# CW308T_LPC55S69_Micro.net
KiCad netlist of a schematic drawn in Altium Designer
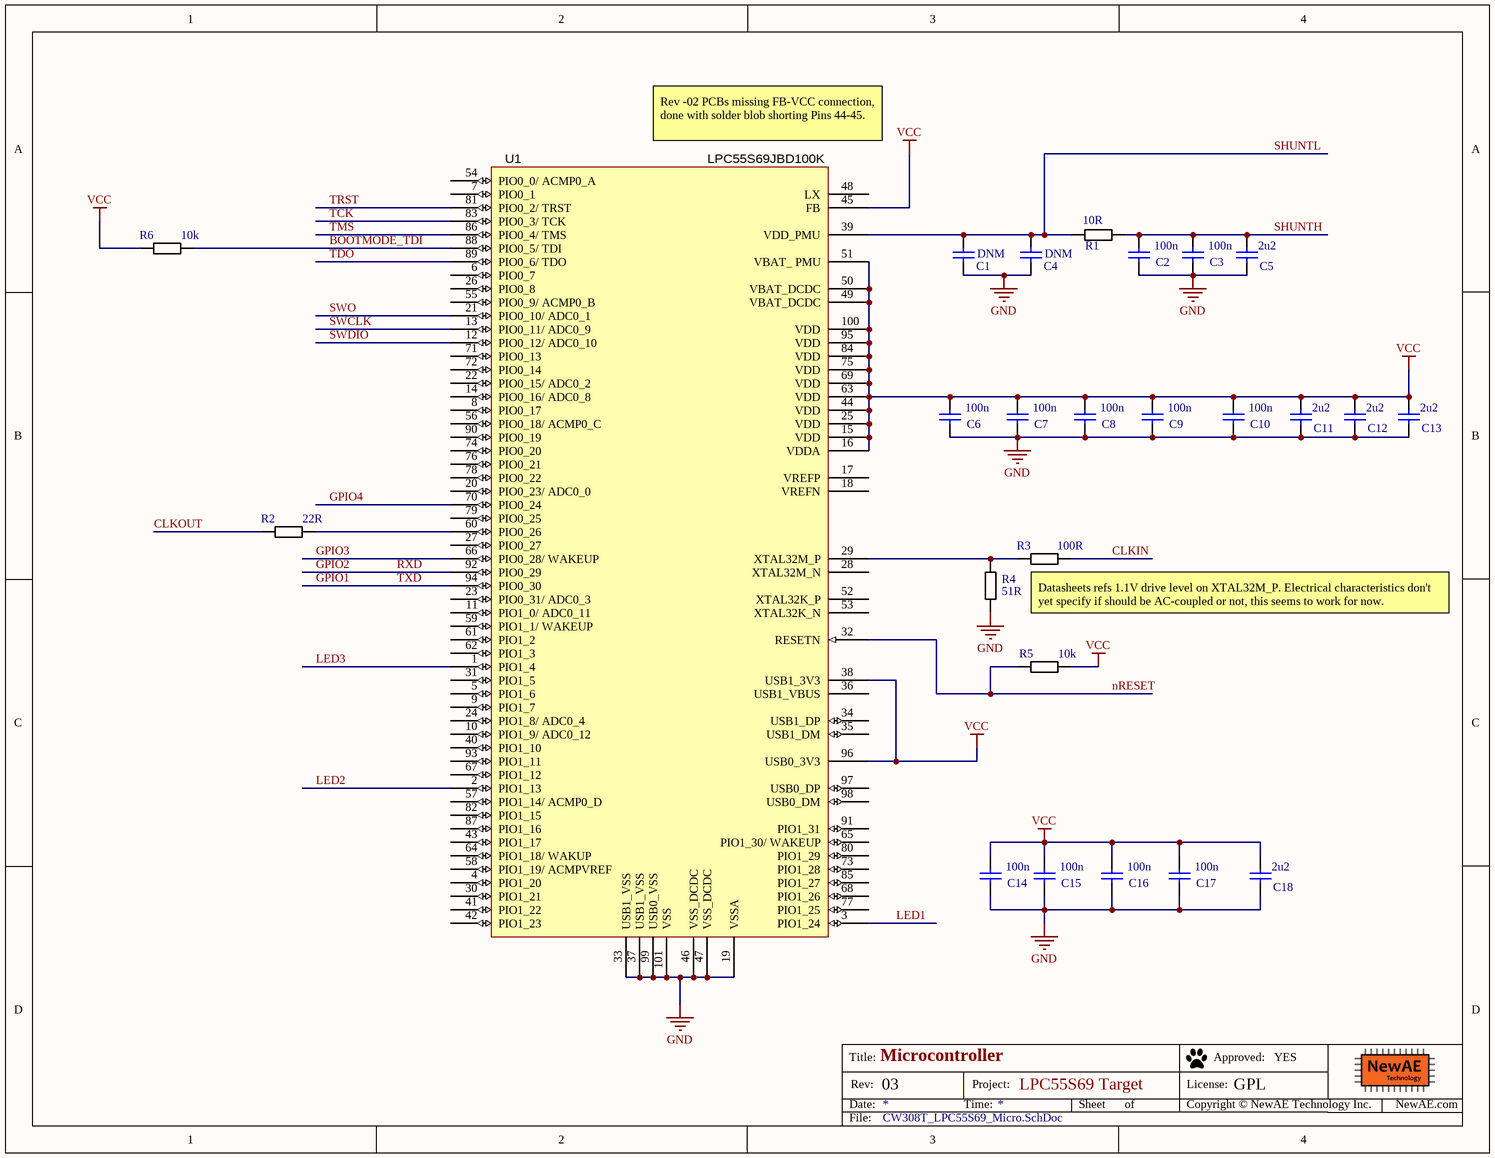
[diagram p0: CW308T_LPC55S69_Micro.SchDoc]

(export (version "E")
  (design (tool "Eeschema 10.0.6"))
  (components
    (comp (ref "C1")
      (value "DNM")
      (footprint "CAPC0603_M")
      (description "DNM, 0603")
      (fields (field (name "PART NUMBER") "CCHIP-DNM-0603"))
      (libsource (lib "NewAE_AltiumLib") (part "CAP"))
    )
    (comp (ref "C2")
      (value "100n")
      (footprint "CAPC0603_M")
      (description "100n, 0603")
      (fields (field (name "PART NUMBER") "CCHIP-100n-0603"))
      (libsource (lib "NewAE_AltiumLib") (part "CAP"))
    )
    (comp (ref "C3")
      (value "100n")
      (footprint "CAPC0603_M")
      (description "100n, 0603")
      (fields (field (name "PART NUMBER") "CCHIP-100n-0603"))
      (libsource (lib "NewAE_AltiumLib") (part "CAP"))
    )
    (comp (ref "C4")
      (value "DNM")
      (footprint "CAPC0603_M")
      (description "DNM, 0603")
      (fields (field (name "PART NUMBER") "CCHIP-DNM-0603"))
      (libsource (lib "NewAE_AltiumLib") (part "CAP"))
    )
    (comp (ref "C5")
      (value "2u2")
      (footprint "CAPC0603_M")
      (description "2u2, 0603")
      (fields (field (name "PART NUMBER") "CCHIP-2u2-0603"))
      (libsource (lib "NewAE_AltiumLib") (part "CAP"))
    )
    (comp (ref "C6")
      (value "100n")
      (footprint "CAPC0603_M")
      (description "100n, 0603")
      (fields (field (name "PART NUMBER") "CCHIP-100n-0603"))
      (libsource (lib "NewAE_AltiumLib") (part "CAP"))
    )
    (comp (ref "C7")
      (value "100n")
      (footprint "CAPC0603_M")
      (description "100n, 0603")
      (fields (field (name "PART NUMBER") "CCHIP-100n-0603"))
      (libsource (lib "NewAE_AltiumLib") (part "CAP"))
    )
    (comp (ref "C8")
      (value "100n")
      (footprint "CAPC0603_M")
      (description "100n, 0603")
      (fields (field (name "PART NUMBER") "CCHIP-100n-0603"))
      (libsource (lib "NewAE_AltiumLib") (part "CAP"))
    )
    (comp (ref "C9")
      (value "100n")
      (footprint "CAPC0603_M")
      (description "100n, 0603")
      (fields (field (name "PART NUMBER") "CCHIP-100n-0603"))
      (libsource (lib "NewAE_AltiumLib") (part "CAP"))
    )
    (comp (ref "C10")
      (value "100n")
      (footprint "CAPC0603_M")
      (description "100n, 0603")
      (fields (field (name "PART NUMBER") "CCHIP-100n-0603"))
      (libsource (lib "NewAE_AltiumLib") (part "CAP"))
    )
    (comp (ref "C11")
      (value "2u2")
      (footprint "CAPC0603_M")
      (description "2u2, 0603")
      (fields (field (name "PART NUMBER") "CCHIP-2u2-0603"))
      (libsource (lib "NewAE_AltiumLib") (part "CAP"))
    )
    (comp (ref "C12")
      (value "2u2")
      (footprint "CAPC0603_M")
      (description "2u2, 0603")
      (fields (field (name "PART NUMBER") "CCHIP-2u2-0603"))
      (libsource (lib "NewAE_AltiumLib") (part "CAP"))
    )
    (comp (ref "C13")
      (value "2u2")
      (footprint "CAPC0603_M")
      (description "2u2, 0603")
      (fields (field (name "PART NUMBER") "CCHIP-2u2-0603"))
      (libsource (lib "NewAE_AltiumLib") (part "CAP"))
    )
    (comp (ref "C14")
      (value "100n")
      (footprint "CAPC0603_M")
      (description "100n, 0603")
      (fields (field (name "PART NUMBER") "CCHIP-100n-0603"))
      (libsource (lib "NewAE_AltiumLib") (part "CAP"))
    )
    (comp (ref "C15")
      (value "100n")
      (footprint "CAPC0603_M")
      (description "100n, 0603")
      (fields (field (name "PART NUMBER") "CCHIP-100n-0603"))
      (libsource (lib "NewAE_AltiumLib") (part "CAP"))
    )
    (comp (ref "C16")
      (value "100n")
      (footprint "CAPC0603_M")
      (description "100n, 0603")
      (fields (field (name "PART NUMBER") "CCHIP-100n-0603"))
      (libsource (lib "NewAE_AltiumLib") (part "CAP"))
    )
    (comp (ref "C17")
      (value "100n")
      (footprint "CAPC0603_M")
      (description "100n, 0603")
      (fields (field (name "PART NUMBER") "CCHIP-100n-0603"))
      (libsource (lib "NewAE_AltiumLib") (part "CAP"))
    )
    (comp (ref "C18")
      (value "2u2")
      (footprint "CAPC0603_M")
      (description "2u2, 0603")
      (fields (field (name "PART NUMBER") "CCHIP-2u2-0603"))
      (libsource (lib "NewAE_AltiumLib") (part "CAP"))
    )
    (comp (ref "R1")
      (value "10R")
      (footprint "RESC1608X55N")
      (description "10R res, 0603, 1%, 1/10W")
      (fields (field (name "PART NUMBER") "RCHIP-10R-0603") (field (name "TOLERANCE") "1%"))
      (libsource (lib "NewAE_AltiumLib") (part "RES-EU"))
    )
    (comp (ref "R2")
      (value "22R")
      (footprint "RESC1608X55N")
      (description "22R res, 0603, 1%, 1/10W")
      (fields (field (name "PART NUMBER") "RCHIP-22R-0603") (field (name "TOLERANCE") "1%"))
      (libsource (lib "NewAE_AltiumLib") (part "RES-EU"))
    )
    (comp (ref "R3")
      (value "100R")
      (footprint "RESC1608X55N")
      (description "100R res, 0603, 1%, 1/10W")
      (fields (field (name "PART NUMBER") "RCHIP-100R-0603") (field (name "TOLERANCE") "1%"))
      (libsource (lib "NewAE_AltiumLib") (part "RES-EU"))
    )
    (comp (ref "R4")
      (value "51R")
      (footprint "RESC1608X55N")
      (description "51R res, 0603, 1%, 1/10W")
      (fields (field (name "PART NUMBER") "RCHIP-51R-0603") (field (name "TOLERANCE") "1%"))
      (libsource (lib "") (part "RES-EU_1"))
    )
    (comp (ref "R5")
      (value "10k")
      (footprint "RESC1608X55N")
      (description "10k res, 0603, 1%, 1/10W")
      (fields (field (name "PART NUMBER") "RCHIP-10K-0603") (field (name "TOLERANCE") "1%"))
      (libsource (lib "NewAE_AltiumLib") (part "RES-EU"))
    )
    (comp (ref "R6")
      (value "10k")
      (footprint "RESC1608X55N")
      (description "10k res, 0603, 1%, 1/10W")
      (fields (field (name "PART NUMBER") "RCHIP-10K-0603") (field (name "TOLERANCE") "1%"))
      (libsource (lib "NewAE_AltiumLib") (part "RES-EU"))
    )
    (comp (ref "U1")
      (value "LPC55S69JBD100K")
      (footprint "PG-TQFP-100-PG-NXP")
      (description "Cortex-m33, dual-core, security")
      (fields (field (name "CREATED BY") "D.GODDARD"))
      (libsource (lib "NewAE_AltiumLib") (part "LPC55S69_LQFP100"))
    )
  )
  (nets
    (net (code "1") (name "/BOOTMODE_TDI") (class "Default")
      (node (ref "R6") (pin "2") (pinfunction "2_2") (pintype "passive"))
      (node (ref "U1") (pin "88") (pinfunction "PIO0_5/_TDI_88") (pintype "bidirectional"))
    )
    (net (code "2") (name "/CLKIN") (class "Default")
      (node (ref "R3") (pin "2") (pinfunction "2_2") (pintype "passive"))
    )
    (net (code "3") (name "/CLKOUT") (class "Default")
      (node (ref "R2") (pin "1") (pinfunction "1_1") (pintype "passive"))
    )
    (net (code "4") (name "/GPIO1") (class "Default")
      (node (ref "U1") (pin "94") (pinfunction "PIO0_30_94") (pintype "bidirectional"))
    )
    (net (code "5") (name "/GPIO2") (class "Default")
      (node (ref "U1") (pin "92") (pinfunction "PIO0_29_92") (pintype "bidirectional"))
    )
    (net (code "6") (name "/GPIO3") (class "Default")
      (node (ref "U1") (pin "66") (pinfunction "PIO0_28/_WAKEUP_66") (pintype "bidirectional"))
    )
    (net (code "7") (name "/GPIO4") (class "Default")
      (node (ref "U1") (pin "70") (pinfunction "PIO0_24_70") (pintype "bidirectional"))
    )
    (net (code "8") (name "/LED1") (class "Default")
      (node (ref "U1") (pin "3") (pinfunction "PIO1_24_3") (pintype "bidirectional"))
    )
    (net (code "9") (name "/LED2") (class "Default")
      (node (ref "U1") (pin "2") (pinfunction "PIO1_13_2") (pintype "bidirectional"))
    )
    (net (code "10") (name "/LED3") (class "Default")
      (node (ref "U1") (pin "1") (pinfunction "PIO1_4_1") (pintype "bidirectional"))
    )
    (net (code "11") (name "/SHUNTH") (class "Default")
      (node (ref "C2") (pin "1") (pinfunction "1_1") (pintype "passive"))
      (node (ref "C3") (pin "1") (pinfunction "1_1") (pintype "passive"))
      (node (ref "C5") (pin "1") (pinfunction "1_1") (pintype "passive"))
      (node (ref "R1") (pin "2") (pinfunction "2_2") (pintype "passive"))
    )
    (net (code "12") (name "/SHUNTL") (class "Default")
      (node (ref "C1") (pin "1") (pinfunction "1_1") (pintype "passive"))
      (node (ref "C4") (pin "1") (pinfunction "1_1") (pintype "passive"))
      (node (ref "R1") (pin "1") (pinfunction "1_1") (pintype "passive"))
      (node (ref "U1") (pin "39") (pinfunction "VDD_PMU_39") (pintype "power_in"))
    )
    (net (code "13") (name "/SWCLK") (class "Default")
      (node (ref "U1") (pin "13") (pinfunction "PIO0_11/_ADC0_9_13") (pintype "bidirectional"))
    )
    (net (code "14") (name "/SWDIO") (class "Default")
      (node (ref "U1") (pin "12") (pinfunction "PIO0_12/_ADC0_10_12") (pintype "bidirectional"))
    )
    (net (code "15") (name "/SWO") (class "Default")
      (node (ref "U1") (pin "21") (pinfunction "PIO0_10/_ADC0_1_21") (pintype "bidirectional"))
    )
    (net (code "16") (name "/TCK") (class "Default")
      (node (ref "U1") (pin "83") (pinfunction "PIO0_3/_TCK_83") (pintype "bidirectional"))
    )
    (net (code "17") (name "/TDO") (class "Default")
      (node (ref "U1") (pin "89") (pinfunction "PIO0_6/_TDO_89") (pintype "bidirectional"))
    )
    (net (code "18") (name "/TMS") (class "Default")
      (node (ref "U1") (pin "86") (pinfunction "PIO0_4/_TMS_86") (pintype "bidirectional"))
    )
    (net (code "19") (name "/TRST") (class "Default")
      (node (ref "U1") (pin "81") (pinfunction "PIO0_2/_TRST_81") (pintype "bidirectional"))
    )
    (net (code "20") (name "/nRESET") (class "Default")
      (node (ref "R5") (pin "1") (pinfunction "1_1") (pintype "passive"))
      (node (ref "U1") (pin "32") (pinfunction "RESETN_32") (pintype "input"))
    )
    (net (code "21") (name "GND") (class "Default")
      (node (ref "C1") (pin "2") (pinfunction "2_2") (pintype "passive"))
      (node (ref "C10") (pin "2") (pinfunction "2_2") (pintype "passive"))
      (node (ref "C11") (pin "2") (pinfunction "2_2") (pintype "passive"))
      (node (ref "C12") (pin "2") (pinfunction "2_2") (pintype "passive"))
      (node (ref "C13") (pin "2") (pinfunction "2_2") (pintype "passive"))
      (node (ref "C14") (pin "2") (pinfunction "2_2") (pintype "passive"))
      (node (ref "C15") (pin "2") (pinfunction "2_2") (pintype "passive"))
      (node (ref "C16") (pin "2") (pinfunction "2_2") (pintype "passive"))
      (node (ref "C17") (pin "2") (pinfunction "2_2") (pintype "passive"))
      (node (ref "C18") (pin "2") (pinfunction "2_2") (pintype "passive"))
      (node (ref "C2") (pin "2") (pinfunction "2_2") (pintype "passive"))
      (node (ref "C3") (pin "2") (pinfunction "2_2") (pintype "passive"))
      (node (ref "C4") (pin "2") (pinfunction "2_2") (pintype "passive"))
      (node (ref "C5") (pin "2") (pinfunction "2_2") (pintype "passive"))
      (node (ref "C6") (pin "2") (pinfunction "2_2") (pintype "passive"))
      (node (ref "C7") (pin "2") (pinfunction "2_2") (pintype "passive"))
      (node (ref "C8") (pin "2") (pinfunction "2_2") (pintype "passive"))
      (node (ref "C9") (pin "2") (pinfunction "2_2") (pintype "passive"))
      (node (ref "R4") (pin "2") (pinfunction "2_2") (pintype "passive"))
      (node (ref "U1") (pin "101") (pinfunction "VSS_101") (pintype "power_in"))
      (node (ref "U1") (pin "19") (pinfunction "VSSA_19") (pintype "power_in"))
      (node (ref "U1") (pin "33") (pinfunction "USB1_VSS_33") (pintype "power_in"))
      (node (ref "U1") (pin "37") (pinfunction "USB1_VSS_37") (pintype "power_in"))
      (node (ref "U1") (pin "46") (pinfunction "VSS_DCDC_46") (pintype "power_in"))
      (node (ref "U1") (pin "47") (pinfunction "VSS_DCDC_47") (pintype "power_in"))
      (node (ref "U1") (pin "99") (pinfunction "USB0_VSS_99") (pintype "power_in"))
    )
    (net (code "22") (name "Net-(U1-PIO0_26)") (class "Default")
      (node (ref "R2") (pin "2") (pinfunction "2_2") (pintype "passive"))
      (node (ref "U1") (pin "60") (pinfunction "PIO0_26_60") (pintype "bidirectional"))
    )
    (net (code "23") (name "Net-(U1-XTAL32M_P)") (class "Default")
      (node (ref "R3") (pin "1") (pinfunction "1_1") (pintype "passive"))
      (node (ref "R4") (pin "1") (pinfunction "1_1") (pintype "passive"))
      (node (ref "U1") (pin "29") (pinfunction "XTAL32M_P_29") (pintype "passive"))
    )
    (net (code "24") (name "VCC") (class "Default")
      (node (ref "C10") (pin "1") (pinfunction "1_1") (pintype "passive"))
      (node (ref "C11") (pin "1") (pinfunction "1_1") (pintype "passive"))
      (node (ref "C12") (pin "1") (pinfunction "1_1") (pintype "passive"))
      (node (ref "C13") (pin "1") (pinfunction "1_1") (pintype "passive"))
      (node (ref "C14") (pin "1") (pinfunction "1_1") (pintype "passive"))
      (node (ref "C15") (pin "1") (pinfunction "1_1") (pintype "passive"))
      (node (ref "C16") (pin "1") (pinfunction "1_1") (pintype "passive"))
      (node (ref "C17") (pin "1") (pinfunction "1_1") (pintype "passive"))
      (node (ref "C18") (pin "1") (pinfunction "1_1") (pintype "passive"))
      (node (ref "C6") (pin "1") (pinfunction "1_1") (pintype "passive"))
      (node (ref "C7") (pin "1") (pinfunction "1_1") (pintype "passive"))
      (node (ref "C8") (pin "1") (pinfunction "1_1") (pintype "passive"))
      (node (ref "C9") (pin "1") (pinfunction "1_1") (pintype "passive"))
      (node (ref "R5") (pin "2") (pinfunction "2_2") (pintype "passive"))
      (node (ref "R6") (pin "1") (pinfunction "1_1") (pintype "passive"))
      (node (ref "U1") (pin "100") (pinfunction "VDD_100") (pintype "power_in"))
      (node (ref "U1") (pin "15") (pinfunction "VDD_15") (pintype "power_in"))
      (node (ref "U1") (pin "16") (pinfunction "VDDA_16") (pintype "power_in"))
      (node (ref "U1") (pin "25") (pinfunction "VDD_25") (pintype "power_in"))
      (node (ref "U1") (pin "38") (pinfunction "USB1_3V3_38") (pintype "power_in"))
      (node (ref "U1") (pin "44") (pinfunction "VDD_44") (pintype "power_in"))
      (node (ref "U1") (pin "45") (pinfunction "FB_45") (pintype "passive"))
      (node (ref "U1") (pin "49") (pinfunction "VBAT_DCDC_49") (pintype "passive"))
      (node (ref "U1") (pin "50") (pinfunction "VBAT_DCDC_50") (pintype "passive"))
      (node (ref "U1") (pin "51") (pinfunction "VBAT__PMU_51") (pintype "power_in"))
      (node (ref "U1") (pin "63") (pinfunction "VDD_63") (pintype "power_in"))
      (node (ref "U1") (pin "69") (pinfunction "VDD_69") (pintype "power_in"))
      (node (ref "U1") (pin "75") (pinfunction "VDD_75") (pintype "power_in"))
      (node (ref "U1") (pin "84") (pinfunction "VDD_84") (pintype "power_in"))
      (node (ref "U1") (pin "95") (pinfunction "VDD_95") (pintype "power_in"))
      (node (ref "U1") (pin "96") (pinfunction "USB0_3V3_96") (pintype "power_in"))
    )
    (net (code "25") (name "unconnected-(U1-LX-Pad48)") (class "Default")
      (node (ref "U1") (pin "48") (pinfunction "LX_48") (pintype "passive"))
    )
    (net (code "26") (name "unconnected-(U1-PIO0_0{slash}_ACMP0_A-Pad54)") (class "Default")
      (node (ref "U1") (pin "54") (pinfunction "PIO0_0/_ACMP0_A_54") (pintype "bidirectional"))
    )
    (net (code "27") (name "unconnected-(U1-PIO0_1-Pad7)") (class "Default")
      (node (ref "U1") (pin "7") (pinfunction "PIO0_1_7") (pintype "bidirectional"))
    )
    (net (code "28") (name "unconnected-(U1-PIO0_7-Pad6)") (class "Default")
      (node (ref "U1") (pin "6") (pinfunction "PIO0_7_6") (pintype "bidirectional"))
    )
    (net (code "29") (name "unconnected-(U1-PIO0_8-Pad26)") (class "Default")
      (node (ref "U1") (pin "26") (pinfunction "PIO0_8_26") (pintype "bidirectional"))
    )
    (net (code "30") (name "unconnected-(U1-PIO0_9{slash}_ACMP0_B-Pad55)") (class "Default")
      (node (ref "U1") (pin "55") (pinfunction "PIO0_9/_ACMP0_B_55") (pintype "bidirectional"))
    )
    (net (code "31") (name "unconnected-(U1-PIO0_13-Pad71)") (class "Default")
      (node (ref "U1") (pin "71") (pinfunction "PIO0_13_71") (pintype "bidirectional"))
    )
    (net (code "32") (name "unconnected-(U1-PIO0_14-Pad72)") (class "Default")
      (node (ref "U1") (pin "72") (pinfunction "PIO0_14_72") (pintype "bidirectional"))
    )
    (net (code "33") (name "unconnected-(U1-PIO0_15{slash}_ADC0_2-Pad22)") (class "Default")
      (node (ref "U1") (pin "22") (pinfunction "PIO0_15/_ADC0_2_22") (pintype "bidirectional"))
    )
    (net (code "34") (name "unconnected-(U1-PIO0_16{slash}_ADC0_8-Pad14)") (class "Default")
      (node (ref "U1") (pin "14") (pinfunction "PIO0_16/_ADC0_8_14") (pintype "bidirectional"))
    )
    (net (code "35") (name "unconnected-(U1-PIO0_17-Pad8)") (class "Default")
      (node (ref "U1") (pin "8") (pinfunction "PIO0_17_8") (pintype "bidirectional"))
    )
    (net (code "36") (name "unconnected-(U1-PIO0_18{slash}_ACMP0_C-Pad56)") (class "Default")
      (node (ref "U1") (pin "56") (pinfunction "PIO0_18/_ACMP0_C_56") (pintype "bidirectional"))
    )
    (net (code "37") (name "unconnected-(U1-PIO0_19-Pad90)") (class "Default")
      (node (ref "U1") (pin "90") (pinfunction "PIO0_19_90") (pintype "bidirectional"))
    )
    (net (code "38") (name "unconnected-(U1-PIO0_20-Pad74)") (class "Default")
      (node (ref "U1") (pin "74") (pinfunction "PIO0_20_74") (pintype "bidirectional"))
    )
    (net (code "39") (name "unconnected-(U1-PIO0_21-Pad76)") (class "Default")
      (node (ref "U1") (pin "76") (pinfunction "PIO0_21_76") (pintype "bidirectional"))
    )
    (net (code "40") (name "unconnected-(U1-PIO0_22-Pad78)") (class "Default")
      (node (ref "U1") (pin "78") (pinfunction "PIO0_22_78") (pintype "bidirectional"))
    )
    (net (code "41") (name "unconnected-(U1-PIO0_23{slash}_ADC0_0-Pad20)") (class "Default")
      (node (ref "U1") (pin "20") (pinfunction "PIO0_23/_ADC0_0_20") (pintype "bidirectional"))
    )
    (net (code "42") (name "unconnected-(U1-PIO0_25-Pad79)") (class "Default")
      (node (ref "U1") (pin "79") (pinfunction "PIO0_25_79") (pintype "bidirectional"))
    )
    (net (code "43") (name "unconnected-(U1-PIO0_27-Pad27)") (class "Default")
      (node (ref "U1") (pin "27") (pinfunction "PIO0_27_27") (pintype "bidirectional"))
    )
    (net (code "44") (name "unconnected-(U1-PIO0_31{slash}_ADC0_3-Pad23)") (class "Default")
      (node (ref "U1") (pin "23") (pinfunction "PIO0_31/_ADC0_3_23") (pintype "bidirectional"))
    )
    (net (code "45") (name "unconnected-(U1-PIO1_0{slash}_ADC0_11-Pad11)") (class "Default")
      (node (ref "U1") (pin "11") (pinfunction "PIO1_0/_ADC0_11_11") (pintype "bidirectional"))
    )
    (net (code "46") (name "unconnected-(U1-PIO1_1{slash}_WAKEUP-Pad59)") (class "Default")
      (node (ref "U1") (pin "59") (pinfunction "PIO1_1/_WAKEUP_59") (pintype "bidirectional"))
    )
    (net (code "47") (name "unconnected-(U1-PIO1_2-Pad61)") (class "Default")
      (node (ref "U1") (pin "61") (pinfunction "PIO1_2_61") (pintype "bidirectional"))
    )
    (net (code "48") (name "unconnected-(U1-PIO1_3-Pad62)") (class "Default")
      (node (ref "U1") (pin "62") (pinfunction "PIO1_3_62") (pintype "bidirectional"))
    )
    (net (code "49") (name "unconnected-(U1-PIO1_5-Pad31)") (class "Default")
      (node (ref "U1") (pin "31") (pinfunction "PIO1_5_31") (pintype "bidirectional"))
    )
    (net (code "50") (name "unconnected-(U1-PIO1_6-Pad5)") (class "Default")
      (node (ref "U1") (pin "5") (pinfunction "PIO1_6_5") (pintype "bidirectional"))
    )
    (net (code "51") (name "unconnected-(U1-PIO1_7-Pad9)") (class "Default")
      (node (ref "U1") (pin "9") (pinfunction "PIO1_7_9") (pintype "bidirectional"))
    )
    (net (code "52") (name "unconnected-(U1-PIO1_8{slash}_ADC0_4-Pad24)") (class "Default")
      (node (ref "U1") (pin "24") (pinfunction "PIO1_8/_ADC0_4_24") (pintype "bidirectional"))
    )
    (net (code "53") (name "unconnected-(U1-PIO1_9{slash}_ADC0_12-Pad10)") (class "Default")
      (node (ref "U1") (pin "10") (pinfunction "PIO1_9/_ADC0_12_10") (pintype "bidirectional"))
    )
    (net (code "54") (name "unconnected-(U1-PIO1_10-Pad40)") (class "Default")
      (node (ref "U1") (pin "40") (pinfunction "PIO1_10_40") (pintype "bidirectional"))
    )
    (net (code "55") (name "unconnected-(U1-PIO1_11-Pad93)") (class "Default")
      (node (ref "U1") (pin "93") (pinfunction "PIO1_11_93") (pintype "bidirectional"))
    )
    (net (code "56") (name "unconnected-(U1-PIO1_12-Pad67)") (class "Default")
      (node (ref "U1") (pin "67") (pinfunction "PIO1_12_67") (pintype "bidirectional"))
    )
    (net (code "57") (name "unconnected-(U1-PIO1_14{slash}_ACMP0_D-Pad57)") (class "Default")
      (node (ref "U1") (pin "57") (pinfunction "PIO1_14/_ACMP0_D_57") (pintype "bidirectional"))
    )
    (net (code "58") (name "unconnected-(U1-PIO1_15-Pad82)") (class "Default")
      (node (ref "U1") (pin "82") (pinfunction "PIO1_15_82") (pintype "bidirectional"))
    )
    (net (code "59") (name "unconnected-(U1-PIO1_16-Pad87)") (class "Default")
      (node (ref "U1") (pin "87") (pinfunction "PIO1_16_87") (pintype "bidirectional"))
    )
    (net (code "60") (name "unconnected-(U1-PIO1_17-Pad43)") (class "Default")
      (node (ref "U1") (pin "43") (pinfunction "PIO1_17_43") (pintype "bidirectional"))
    )
    (net (code "61") (name "unconnected-(U1-PIO1_18{slash}_WAKUP-Pad64)") (class "Default")
      (node (ref "U1") (pin "64") (pinfunction "PIO1_18/_WAKUP_64") (pintype "bidirectional"))
    )
    (net (code "62") (name "unconnected-(U1-PIO1_19{slash}_ACMPVREF-Pad58)") (class "Default")
      (node (ref "U1") (pin "58") (pinfunction "PIO1_19/_ACMPVREF_58") (pintype "bidirectional"))
    )
    (net (code "63") (name "unconnected-(U1-PIO1_20-Pad4)") (class "Default")
      (node (ref "U1") (pin "4") (pinfunction "PIO1_20_4") (pintype "bidirectional"))
    )
    (net (code "64") (name "unconnected-(U1-PIO1_21-Pad30)") (class "Default")
      (node (ref "U1") (pin "30") (pinfunction "PIO1_21_30") (pintype "bidirectional"))
    )
    (net (code "65") (name "unconnected-(U1-PIO1_22-Pad41)") (class "Default")
      (node (ref "U1") (pin "41") (pinfunction "PIO1_22_41") (pintype "bidirectional"))
    )
    (net (code "66") (name "unconnected-(U1-PIO1_23-Pad42)") (class "Default")
      (node (ref "U1") (pin "42") (pinfunction "PIO1_23_42") (pintype "bidirectional"))
    )
    (net (code "67") (name "unconnected-(U1-PIO1_25-Pad77)") (class "Default")
      (node (ref "U1") (pin "77") (pinfunction "PIO1_25_77") (pintype "bidirectional"))
    )
    (net (code "68") (name "unconnected-(U1-PIO1_26-Pad68)") (class "Default")
      (node (ref "U1") (pin "68") (pinfunction "PIO1_26_68") (pintype "bidirectional"))
    )
    (net (code "69") (name "unconnected-(U1-PIO1_27-Pad85)") (class "Default")
      (node (ref "U1") (pin "85") (pinfunction "PIO1_27_85") (pintype "bidirectional"))
    )
    (net (code "70") (name "unconnected-(U1-PIO1_28-Pad73)") (class "Default")
      (node (ref "U1") (pin "73") (pinfunction "PIO1_28_73") (pintype "bidirectional"))
    )
    (net (code "71") (name "unconnected-(U1-PIO1_29-Pad80)") (class "Default")
      (node (ref "U1") (pin "80") (pinfunction "PIO1_29_80") (pintype "bidirectional"))
    )
    (net (code "72") (name "unconnected-(U1-PIO1_30{slash}_WAKEUP-Pad65)") (class "Default")
      (node (ref "U1") (pin "65") (pinfunction "PIO1_30/_WAKEUP_65") (pintype "bidirectional"))
    )
    (net (code "73") (name "unconnected-(U1-PIO1_31-Pad91)") (class "Default")
      (node (ref "U1") (pin "91") (pinfunction "PIO1_31_91") (pintype "bidirectional"))
    )
    (net (code "74") (name "unconnected-(U1-USB0_DM-Pad98)") (class "Default")
      (node (ref "U1") (pin "98") (pinfunction "USB0_DM_98") (pintype "bidirectional"))
    )
    (net (code "75") (name "unconnected-(U1-USB0_DP-Pad97)") (class "Default")
      (node (ref "U1") (pin "97") (pinfunction "USB0_DP_97") (pintype "bidirectional"))
    )
    (net (code "76") (name "unconnected-(U1-USB1_DM-Pad35)") (class "Default")
      (node (ref "U1") (pin "35") (pinfunction "USB1_DM_35") (pintype "bidirectional"))
    )
    (net (code "77") (name "unconnected-(U1-USB1_DP-Pad34)") (class "Default")
      (node (ref "U1") (pin "34") (pinfunction "USB1_DP_34") (pintype "bidirectional"))
    )
    (net (code "78") (name "unconnected-(U1-USB1_VBUS-Pad36)") (class "Default")
      (node (ref "U1") (pin "36") (pinfunction "USB1_VBUS_36") (pintype "passive"))
    )
    (net (code "79") (name "unconnected-(U1-VREFN-Pad18)") (class "Default")
      (node (ref "U1") (pin "18") (pinfunction "VREFN_18") (pintype "passive"))
    )
    (net (code "80") (name "unconnected-(U1-VREFP-Pad17)") (class "Default")
      (node (ref "U1") (pin "17") (pinfunction "VREFP_17") (pintype "passive"))
    )
    (net (code "81") (name "unconnected-(U1-XTAL32K_N-Pad53)") (class "Default")
      (node (ref "U1") (pin "53") (pinfunction "XTAL32K_N_53") (pintype "passive"))
    )
    (net (code "82") (name "unconnected-(U1-XTAL32K_P-Pad52)") (class "Default")
      (node (ref "U1") (pin "52") (pinfunction "XTAL32K_P_52") (pintype "passive"))
    )
    (net (code "83") (name "unconnected-(U1-XTAL32M_N-Pad28)") (class "Default")
      (node (ref "U1") (pin "28") (pinfunction "XTAL32M_N_28") (pintype "passive"))
    )
  )
)
